# omo_v2.net
KiCad netlist of a schematic drawn in EAGLE
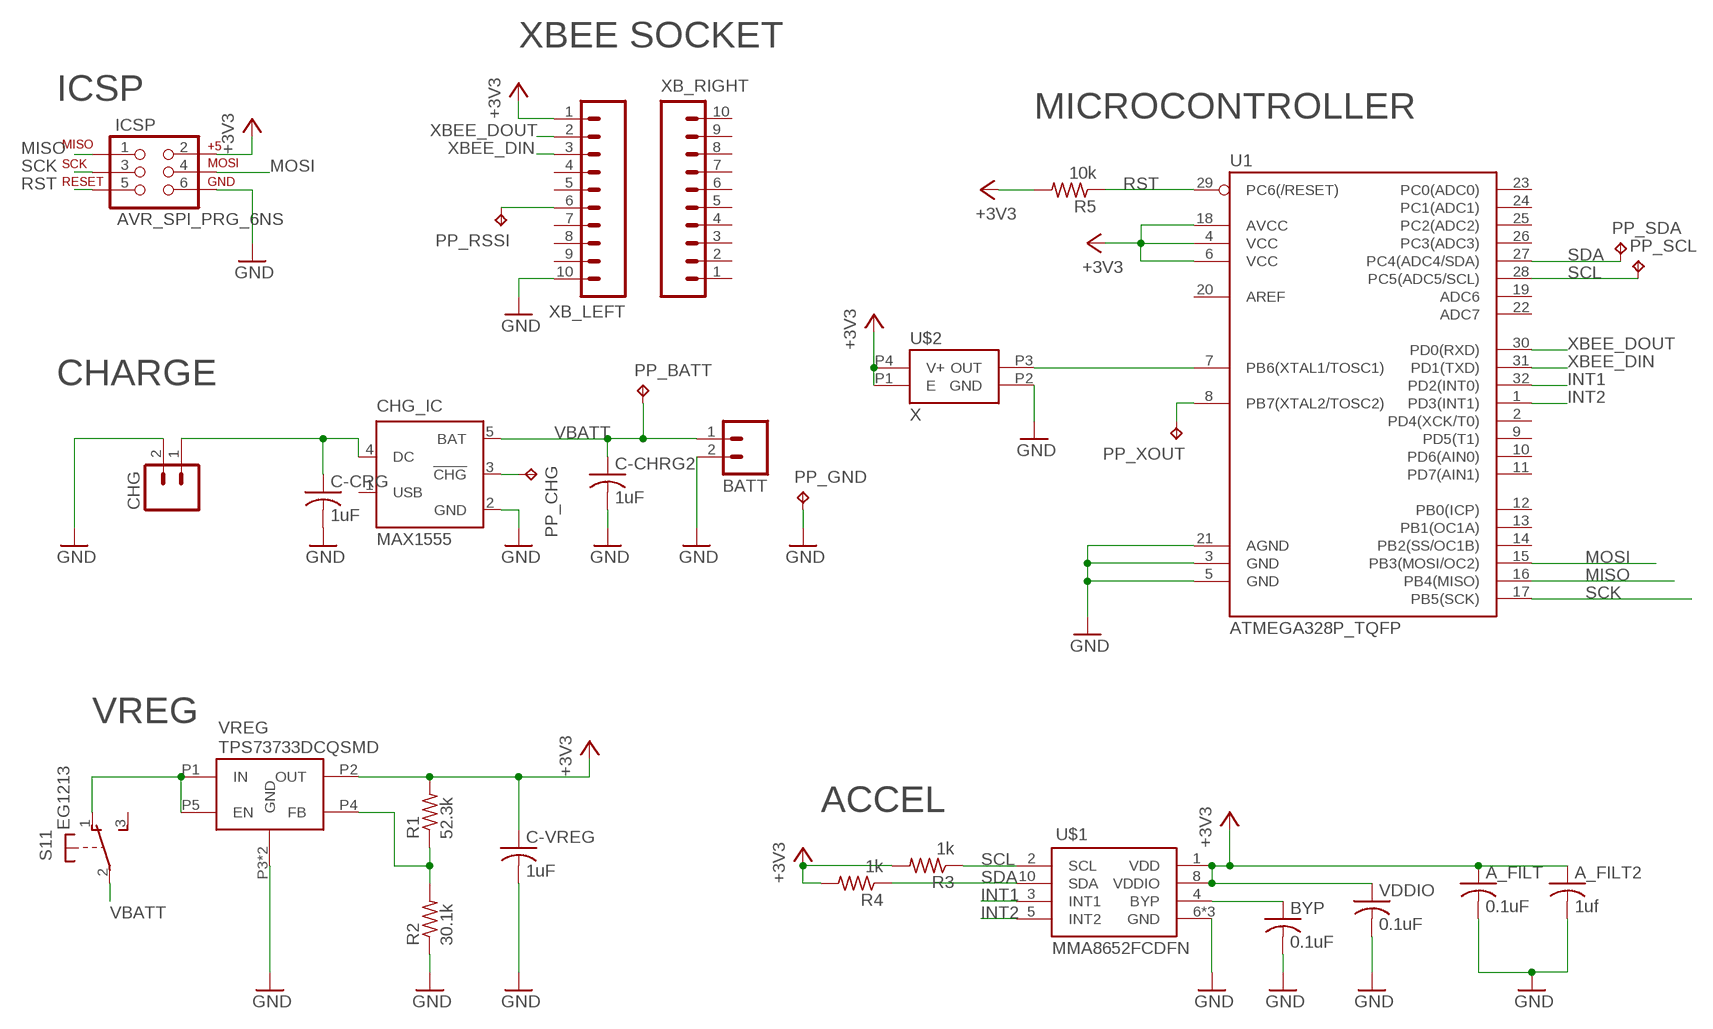
[diagram p0: schematic, sheet 1]

(export (version "E")
  (design (tool "Eeschema 10.0.6"))
  (components
    (comp (ref "A_FILT")
      (value "0.1uF")
      (footprint "eagle-import:C0805")
      (libsource (lib "eagle-import") (part "C-USC0805"))
    )
    (comp (ref "A_FILT2")
      (value "1uf")
      (footprint "eagle-import:C0805")
      (libsource (lib "eagle-import") (part "C-USC0805"))
    )
    (comp (ref "BATT")
      (value "M02-JST-2-PTH-NO_SILK")
      (footprint "eagle-import:JST-2-PTH-NS")
      (libsource (lib "eagle-import") (part "M02-JST-2-PTH-NO_SILK"))
    )
    (comp (ref "BYP")
      (value "0.1uF")
      (footprint "eagle-import:C0805")
      (libsource (lib "eagle-import") (part "C-USC0805"))
    )
    (comp (ref "C-CHRG2")
      (value "1uF")
      (footprint "eagle-import:C0805")
      (libsource (lib "eagle-import") (part "C-USC0805"))
    )
    (comp (ref "C-CRG")
      (value "1uF")
      (footprint "eagle-import:C0805")
      (libsource (lib "eagle-import") (part "C-USC0805"))
    )
    (comp (ref "C-VREG")
      (value "1uF")
      (footprint "eagle-import:C0805")
      (libsource (lib "eagle-import") (part "C-USC0805"))
    )
    (comp (ref "CHG")
      (value "M02-JST-2-PTH-NO_SILK")
      (footprint "eagle-import:JST-2-PTH-NS")
      (libsource (lib "eagle-import") (part "M02-JST-2-PTH-NO_SILK"))
    )
    (comp (ref "CHG_IC")
      (value "MAX1555")
      (footprint "eagle-import:SOT23-5L")
      (fields (field (name "MF") "MAXIM") (field (name "MPN") "MAX1555EZK+T"))
      (libsource (lib "eagle-import") (part "MAX1555"))
    )
    (comp (ref "ICSP")
      (value "AVR_SPI_PRG_6NS")
      (footprint "eagle-import:2X3-NS")
      (libsource (lib "eagle-import") (part "AVR_SPI_PRG_6NS"))
    )
    (comp (ref "PP_BATT")
      (value "TPB1,27")
      (footprint "eagle-import:B1,27")
      (libsource (lib "eagle-import") (part "TPB1,27"))
    )
    (comp (ref "PP_CHG")
      (value "TPB1,27")
      (footprint "eagle-import:B1,27")
      (libsource (lib "eagle-import") (part "TPB1,27"))
    )
    (comp (ref "PP_GND")
      (value "TPB1,27")
      (footprint "eagle-import:B1,27")
      (libsource (lib "eagle-import") (part "TPB1,27"))
    )
    (comp (ref "PP_RSSI")
      (value "TPB1,27")
      (footprint "eagle-import:B1,27")
      (libsource (lib "eagle-import") (part "TPB1,27"))
    )
    (comp (ref "PP_SCL")
      (value "TPB1,27")
      (footprint "eagle-import:B1,27")
      (libsource (lib "eagle-import") (part "TPB1,27"))
    )
    (comp (ref "PP_SDA")
      (value "TPB1,27")
      (footprint "eagle-import:B1,27")
      (libsource (lib "eagle-import") (part "TPB1,27"))
    )
    (comp (ref "PP_XOUT")
      (value "TPB1,27")
      (footprint "eagle-import:B1,27")
      (libsource (lib "eagle-import") (part "TPB1,27"))
    )
    (comp (ref "R1")
      (value "52.3k")
      (footprint "eagle-import:R0805")
      (libsource (lib "eagle-import") (part "R-US_R0805"))
    )
    (comp (ref "R2")
      (value "30.1k")
      (footprint "eagle-import:R0805")
      (libsource (lib "eagle-import") (part "R-US_R0805"))
    )
    (comp (ref "R3")
      (value "1k")
      (footprint "eagle-import:R0805")
      (libsource (lib "eagle-import") (part "R-US_R0805"))
    )
    (comp (ref "R4")
      (value "1k")
      (footprint "eagle-import:R0805")
      (libsource (lib "eagle-import") (part "R-US_R0805"))
    )
    (comp (ref "R5")
      (value "10k")
      (footprint "eagle-import:R0805")
      (libsource (lib "eagle-import") (part "R-US_R0805"))
    )
    (comp (ref "S1")
      (value "EG1213")
      (footprint "eagle-import:EG1213")
      (libsource (lib "eagle-import") (part "EG1213"))
    )
    (comp (ref "U$1")
      (value "MMA8652FCDFN")
      (footprint "eagle-import:MMA8652FC")
      (libsource (lib "eagle-import") (part "MMA8652FCDFN"))
    )
    (comp (ref "U$2")
      (value "X")
      (footprint "eagle-import:QX3-OSC-3.2X2.5")
      (libsource (lib "eagle-import") (part "QX3-XSTAL-3V33V3-SMD"))
    )
    (comp (ref "U1")
      (value "ATMEGA328P_TQFP")
      (footprint "eagle-import:TQFP32-08")
      (libsource (lib "eagle-import") (part "ATMEGA328P_TQFP"))
    )
    (comp (ref "VDDIO")
      (value "0.1uF")
      (footprint "eagle-import:C0805")
      (libsource (lib "eagle-import") (part "C-USC0805"))
    )
    (comp (ref "VREG")
      (value "TPS73733DCQSMD")
      (footprint "eagle-import:SOT-223-6")
      (libsource (lib "eagle-import") (part "TPS73733DCQSMD"))
    )
    (comp (ref "XB_LEFT")
      (value "M102MM")
      (footprint "eagle-import:1X10-2MM")
      (libsource (lib "eagle-import") (part "M102MM"))
    )
    (comp (ref "XB_RIGHT")
      (value "M102MM")
      (footprint "eagle-import:1X10-2MM")
      (libsource (lib "eagle-import") (part "M102MM"))
    )
  )
  (nets
    (net (code "1") (name "+3V3") (class "Default")
      (node (ref "A_FILT") (pin "1") (pinfunction "1_1") (pintype "passive"))
      (node (ref "A_FILT2") (pin "1") (pinfunction "1_1") (pintype "passive"))
      (node (ref "C-VREG") (pin "1") (pinfunction "1_1") (pintype "passive"))
      (node (ref "ICSP") (pin "2") (pinfunction "2_2") (pintype "passive"))
      (node (ref "R1") (pin "2") (pinfunction "2_2") (pintype "passive"))
      (node (ref "R3") (pin "2") (pinfunction "2_2") (pintype "passive"))
      (node (ref "R4") (pin "2") (pinfunction "2_2") (pintype "passive"))
      (node (ref "R5") (pin "2") (pinfunction "2_2") (pintype "passive"))
      (node (ref "U$1") (pin "1") (pinfunction "VDD_1") (pintype "bidirectional"))
      (node (ref "U$1") (pin "8") (pinfunction "VDDIO_8") (pintype "bidirectional"))
      (node (ref "U$2") (pin "P1") (pinfunction "E_P1") (pintype "bidirectional"))
      (node (ref "U$2") (pin "P4") (pinfunction "V+_P4") (pintype "bidirectional"))
      (node (ref "U1") (pin "18") (pinfunction "AVCC_18") (pintype "bidirectional"))
      (node (ref "U1") (pin "4") (pinfunction "VCC_4") (pintype "bidirectional"))
      (node (ref "U1") (pin "6") (pinfunction "VCC_6") (pintype "bidirectional"))
      (node (ref "VDDIO") (pin "1") (pinfunction "1_1") (pintype "passive"))
      (node (ref "VREG") (pin "P2") (pinfunction "OUT_P2") (pintype "bidirectional"))
      (node (ref "XB_LEFT") (pin "1") (pinfunction "1_1") (pintype "passive"))
    )
    (net (code "2") (name "/INT1") (class "Default")
      (node (ref "U$1") (pin "3") (pinfunction "INT1_3") (pintype "bidirectional"))
      (node (ref "U1") (pin "32") (pinfunction "PD2(INT0)_32") (pintype "bidirectional"))
    )
    (net (code "3") (name "/INT2") (class "Default")
      (node (ref "U$1") (pin "5") (pinfunction "INT2_5") (pintype "bidirectional"))
      (node (ref "U1") (pin "1") (pinfunction "PD3(INT1)_1") (pintype "bidirectional"))
    )
    (net (code "4") (name "/MISO") (class "Default")
      (node (ref "ICSP") (pin "1") (pinfunction "1_1") (pintype "passive"))
      (node (ref "U1") (pin "16") (pinfunction "PB4(MISO)_16") (pintype "bidirectional"))
    )
    (net (code "5") (name "/MOSI") (class "Default")
      (node (ref "ICSP") (pin "4") (pinfunction "4_4") (pintype "passive"))
      (node (ref "U1") (pin "15") (pinfunction "PB3(MOSI/OC2)_15") (pintype "bidirectional"))
    )
    (net (code "6") (name "/RST") (class "Default")
      (node (ref "ICSP") (pin "5") (pinfunction "5_5") (pintype "passive"))
      (node (ref "R5") (pin "1") (pinfunction "1_1") (pintype "passive"))
      (node (ref "U1") (pin "29") (pinfunction "PC6(/RESET)_29") (pintype "bidirectional"))
    )
    (net (code "7") (name "/SCK") (class "Default")
      (node (ref "ICSP") (pin "3") (pinfunction "3_3") (pintype "passive"))
      (node (ref "U1") (pin "17") (pinfunction "PB5(SCK)_17") (pintype "bidirectional"))
    )
    (net (code "8") (name "/SCL") (class "Default")
      (node (ref "PP_SCL") (pin "TP") (pinfunction "TP_TP") (pintype "input"))
      (node (ref "R3") (pin "1") (pinfunction "1_1") (pintype "passive"))
      (node (ref "U$1") (pin "2") (pinfunction "SCL_2") (pintype "bidirectional"))
      (node (ref "U1") (pin "28") (pinfunction "PC5(ADC5/SCL)_28") (pintype "bidirectional"))
    )
    (net (code "9") (name "/SDA") (class "Default")
      (node (ref "PP_SDA") (pin "TP") (pinfunction "TP_TP") (pintype "input"))
      (node (ref "R4") (pin "1") (pinfunction "1_1") (pintype "passive"))
      (node (ref "U$1") (pin "10") (pinfunction "SDA_10") (pintype "bidirectional"))
      (node (ref "U1") (pin "27") (pinfunction "PC4(ADC4/SDA)_27") (pintype "bidirectional"))
    )
    (net (code "10") (name "/VBATT") (class "Default")
      (node (ref "BATT") (pin "1") (pinfunction "1_1") (pintype "passive"))
      (node (ref "C-CHRG2") (pin "1") (pinfunction "1_1") (pintype "passive"))
      (node (ref "CHG_IC") (pin "5") (pinfunction "BAT_5") (pintype "passive"))
      (node (ref "PP_BATT") (pin "TP") (pinfunction "TP_TP") (pintype "input"))
      (node (ref "S1") (pin "2") (pinfunction "P_2") (pintype "passive"))
    )
    (net (code "11") (name "/XBEE_DIN") (class "Default")
      (node (ref "U1") (pin "31") (pinfunction "PD1(TXD)_31") (pintype "bidirectional"))
      (node (ref "XB_LEFT") (pin "3") (pinfunction "3_3") (pintype "passive"))
    )
    (net (code "12") (name "/XBEE_DOUT") (class "Default")
      (node (ref "U1") (pin "30") (pinfunction "PD0(RXD)_30") (pintype "bidirectional"))
      (node (ref "XB_LEFT") (pin "2") (pinfunction "2_2") (pintype "passive"))
    )
    (net (code "13") (name "GND") (class "Default")
      (node (ref "A_FILT") (pin "2") (pinfunction "2_2") (pintype "passive"))
      (node (ref "A_FILT2") (pin "2") (pinfunction "2_2") (pintype "passive"))
      (node (ref "BATT") (pin "2") (pinfunction "2_2") (pintype "passive"))
      (node (ref "BYP") (pin "2") (pinfunction "2_2") (pintype "passive"))
      (node (ref "C-CHRG2") (pin "2") (pinfunction "2_2") (pintype "passive"))
      (node (ref "C-CRG") (pin "2") (pinfunction "2_2") (pintype "passive"))
      (node (ref "C-VREG") (pin "2") (pinfunction "2_2") (pintype "passive"))
      (node (ref "CHG") (pin "2") (pinfunction "2_2") (pintype "passive"))
      (node (ref "CHG_IC") (pin "2") (pinfunction "GND_2") (pintype "power_in"))
      (node (ref "ICSP") (pin "6") (pinfunction "6_6") (pintype "passive"))
      (node (ref "PP_GND") (pin "TP") (pinfunction "TP_TP") (pintype "input"))
      (node (ref "R2") (pin "1") (pinfunction "1_1") (pintype "passive"))
      (node (ref "U$1") (pin "6") (pinfunction "GND_6") (pintype "bidirectional"))
      (node (ref "U$1") (pin "7") (pinfunction "GND_7") (pintype "bidirectional"))
      (node (ref "U$1") (pin "9") (pinfunction "GND_9") (pintype "bidirectional"))
      (node (ref "U$2") (pin "P2") (pinfunction "GND_P2") (pintype "bidirectional"))
      (node (ref "U1") (pin "21") (pinfunction "AGND_21") (pintype "bidirectional"))
      (node (ref "U1") (pin "3") (pinfunction "GND_3") (pintype "bidirectional"))
      (node (ref "U1") (pin "5") (pinfunction "GND_5") (pintype "bidirectional"))
      (node (ref "VDDIO") (pin "2") (pinfunction "2_2") (pintype "passive"))
      (node (ref "VREG") (pin "P3") (pinfunction "GND_P3") (pintype "bidirectional"))
      (node (ref "VREG") (pin "P6") (pinfunction "GND_P6") (pintype "bidirectional"))
      (node (ref "XB_LEFT") (pin "10") (pinfunction "10_10") (pintype "passive"))
    )
    (net (code "14") (name "Net-(CHG_IC-DC)") (class "Default")
      (node (ref "C-CRG") (pin "1") (pinfunction "1_1") (pintype "passive"))
      (node (ref "CHG") (pin "1") (pinfunction "1_1") (pintype "passive"))
      (node (ref "CHG_IC") (pin "4") (pinfunction "DC_4") (pintype "input"))
    )
    (net (code "15") (name "Net-(CHG_IC-~{CHG})") (class "Default")
      (node (ref "CHG_IC") (pin "3") (pinfunction "~{CHG}_3") (pintype "output"))
      (node (ref "PP_CHG") (pin "TP") (pinfunction "TP_TP") (pintype "input"))
    )
    (net (code "16") (name "Net-(PP_RSSI-PadTP)") (class "Default")
      (node (ref "PP_RSSI") (pin "TP") (pinfunction "TP_TP") (pintype "input"))
      (node (ref "XB_LEFT") (pin "6") (pinfunction "6_6") (pintype "passive"))
    )
    (net (code "17") (name "Net-(S1A-O)") (class "Default")
      (node (ref "S1") (pin "1") (pinfunction "O_1") (pintype "passive"))
      (node (ref "VREG") (pin "P1") (pinfunction "IN_P1") (pintype "bidirectional"))
      (node (ref "VREG") (pin "P5") (pinfunction "EN_P5") (pintype "bidirectional"))
    )
    (net (code "18") (name "Net-(U$1-BYP)") (class "Default")
      (node (ref "BYP") (pin "1") (pinfunction "1_1") (pintype "passive"))
      (node (ref "U$1") (pin "4") (pinfunction "BYP_4") (pintype "bidirectional"))
    )
    (net (code "19") (name "Net-(U$2-OUT)") (class "Default")
      (node (ref "U$2") (pin "P3") (pinfunction "OUT_P3") (pintype "bidirectional"))
      (node (ref "U1") (pin "7") (pinfunction "PB6(XTAL1/TOSC1)_7") (pintype "bidirectional"))
    )
    (net (code "20") (name "Net-(U1-PB7(XTAL2{slash}TOSC2))") (class "Default")
      (node (ref "PP_XOUT") (pin "TP") (pinfunction "TP_TP") (pintype "input"))
      (node (ref "U1") (pin "8") (pinfunction "PB7(XTAL2/TOSC2)_8") (pintype "bidirectional"))
    )
    (net (code "21") (name "Net-(VREG-FB)") (class "Default")
      (node (ref "R1") (pin "1") (pinfunction "1_1") (pintype "passive"))
      (node (ref "R2") (pin "2") (pinfunction "2_2") (pintype "passive"))
      (node (ref "VREG") (pin "P4") (pinfunction "FB_P4") (pintype "bidirectional"))
    )
    (net (code "22") (name "unconnected-(CHG_IC-USB-Pad1)") (class "Default")
      (node (ref "CHG_IC") (pin "1") (pinfunction "USB_1") (pintype "input"))
    )
    (net (code "23") (name "unconnected-(S1A-S-Pad3)") (class "Default")
      (node (ref "S1") (pin "3") (pinfunction "S_3") (pintype "passive"))
    )
    (net (code "24") (name "unconnected-(U1-ADC6-Pad19)") (class "Default")
      (node (ref "U1") (pin "19") (pinfunction "ADC6_19") (pintype "bidirectional"))
    )
    (net (code "25") (name "unconnected-(U1-ADC7-Pad22)") (class "Default")
      (node (ref "U1") (pin "22") (pinfunction "ADC7_22") (pintype "bidirectional"))
    )
    (net (code "26") (name "unconnected-(U1-AREF-Pad20)") (class "Default")
      (node (ref "U1") (pin "20") (pinfunction "AREF_20") (pintype "bidirectional"))
    )
    (net (code "27") (name "unconnected-(U1-PB0(ICP)-Pad12)") (class "Default")
      (node (ref "U1") (pin "12") (pinfunction "PB0(ICP)_12") (pintype "bidirectional"))
    )
    (net (code "28") (name "unconnected-(U1-PB1(OC1A)-Pad13)") (class "Default")
      (node (ref "U1") (pin "13") (pinfunction "PB1(OC1A)_13") (pintype "bidirectional"))
    )
    (net (code "29") (name "unconnected-(U1-PB2(SS{slash}OC1B)-Pad14)") (class "Default")
      (node (ref "U1") (pin "14") (pinfunction "PB2(SS/OC1B)_14") (pintype "bidirectional"))
    )
    (net (code "30") (name "unconnected-(U1-PC0(ADC0)-Pad23)") (class "Default")
      (node (ref "U1") (pin "23") (pinfunction "PC0(ADC0)_23") (pintype "bidirectional"))
    )
    (net (code "31") (name "unconnected-(U1-PC1(ADC1)-Pad24)") (class "Default")
      (node (ref "U1") (pin "24") (pinfunction "PC1(ADC1)_24") (pintype "bidirectional"))
    )
    (net (code "32") (name "unconnected-(U1-PC2(ADC2)-Pad25)") (class "Default")
      (node (ref "U1") (pin "25") (pinfunction "PC2(ADC2)_25") (pintype "bidirectional"))
    )
    (net (code "33") (name "unconnected-(U1-PC3(ADC3)-Pad26)") (class "Default")
      (node (ref "U1") (pin "26") (pinfunction "PC3(ADC3)_26") (pintype "bidirectional"))
    )
    (net (code "34") (name "unconnected-(U1-PD4(XCK{slash}T0)-Pad2)") (class "Default")
      (node (ref "U1") (pin "2") (pinfunction "PD4(XCK/T0)_2") (pintype "bidirectional"))
    )
    (net (code "35") (name "unconnected-(U1-PD5(T1)-Pad9)") (class "Default")
      (node (ref "U1") (pin "9") (pinfunction "PD5(T1)_9") (pintype "bidirectional"))
    )
    (net (code "36") (name "unconnected-(U1-PD6(AIN0)-Pad10)") (class "Default")
      (node (ref "U1") (pin "10") (pinfunction "PD6(AIN0)_10") (pintype "bidirectional"))
    )
    (net (code "37") (name "unconnected-(U1-PD7(AIN1)-Pad11)") (class "Default")
      (node (ref "U1") (pin "11") (pinfunction "PD7(AIN1)_11") (pintype "bidirectional"))
    )
    (net (code "38") (name "unconnected-(XB_LEFT-Pad4)") (class "Default")
      (node (ref "XB_LEFT") (pin "4") (pinfunction "4_4") (pintype "passive"))
    )
    (net (code "39") (name "unconnected-(XB_LEFT-Pad5)") (class "Default")
      (node (ref "XB_LEFT") (pin "5") (pinfunction "5_5") (pintype "passive"))
    )
    (net (code "40") (name "unconnected-(XB_LEFT-Pad7)") (class "Default")
      (node (ref "XB_LEFT") (pin "7") (pinfunction "7_7") (pintype "passive"))
    )
    (net (code "41") (name "unconnected-(XB_LEFT-Pad8)") (class "Default")
      (node (ref "XB_LEFT") (pin "8") (pinfunction "8_8") (pintype "passive"))
    )
    (net (code "42") (name "unconnected-(XB_LEFT-Pad9)") (class "Default")
      (node (ref "XB_LEFT") (pin "9") (pinfunction "9_9") (pintype "passive"))
    )
    (net (code "43") (name "unconnected-(XB_RIGHT-Pad1)") (class "Default")
      (node (ref "XB_RIGHT") (pin "1") (pinfunction "1_1") (pintype "passive"))
    )
    (net (code "44") (name "unconnected-(XB_RIGHT-Pad2)") (class "Default")
      (node (ref "XB_RIGHT") (pin "2") (pinfunction "2_2") (pintype "passive"))
    )
    (net (code "45") (name "unconnected-(XB_RIGHT-Pad3)") (class "Default")
      (node (ref "XB_RIGHT") (pin "3") (pinfunction "3_3") (pintype "passive"))
    )
    (net (code "46") (name "unconnected-(XB_RIGHT-Pad4)") (class "Default")
      (node (ref "XB_RIGHT") (pin "4") (pinfunction "4_4") (pintype "passive"))
    )
    (net (code "47") (name "unconnected-(XB_RIGHT-Pad5)") (class "Default")
      (node (ref "XB_RIGHT") (pin "5") (pinfunction "5_5") (pintype "passive"))
    )
    (net (code "48") (name "unconnected-(XB_RIGHT-Pad6)") (class "Default")
      (node (ref "XB_RIGHT") (pin "6") (pinfunction "6_6") (pintype "passive"))
    )
    (net (code "49") (name "unconnected-(XB_RIGHT-Pad7)") (class "Default")
      (node (ref "XB_RIGHT") (pin "7") (pinfunction "7_7") (pintype "passive"))
    )
    (net (code "50") (name "unconnected-(XB_RIGHT-Pad8)") (class "Default")
      (node (ref "XB_RIGHT") (pin "8") (pinfunction "8_8") (pintype "passive"))
    )
    (net (code "51") (name "unconnected-(XB_RIGHT-Pad9)") (class "Default")
      (node (ref "XB_RIGHT") (pin "9") (pinfunction "9_9") (pintype "passive"))
    )
    (net (code "52") (name "unconnected-(XB_RIGHT-Pad10)") (class "Default")
      (node (ref "XB_RIGHT") (pin "10") (pinfunction "10_10") (pintype "passive"))
    )
  )
)
